# dirtcheaprx.net
KiCad netlist of a schematic drawn in EAGLE
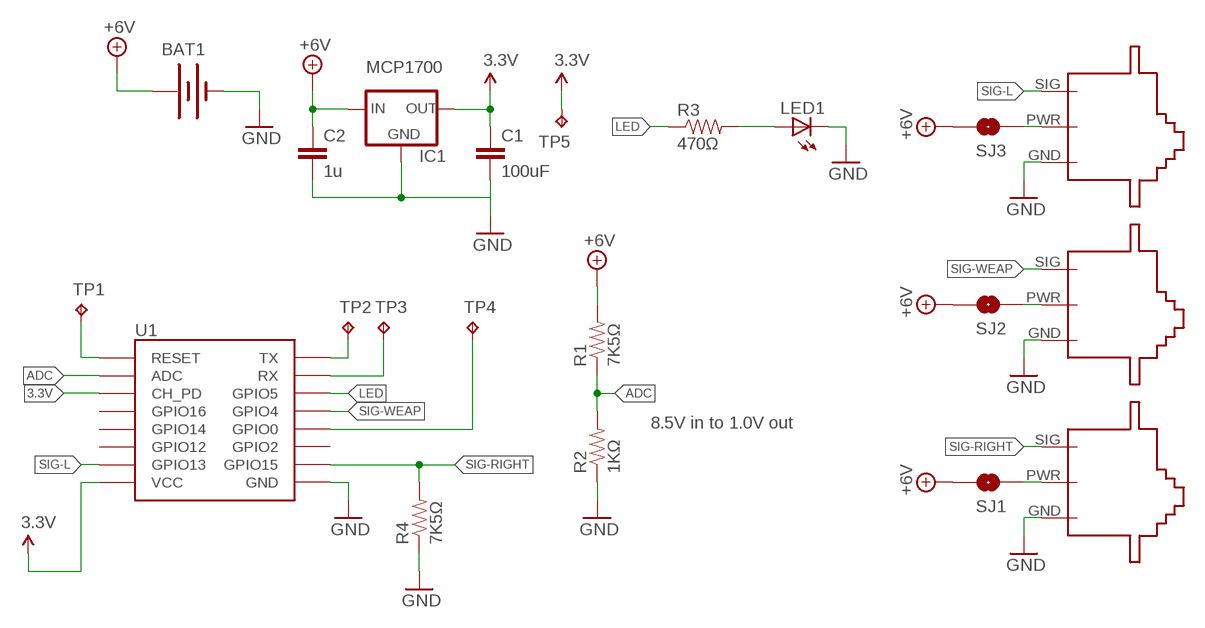
[diagram p0: schematic, sheet 1]

(export (version "E")
  (design (tool "Eeschema 10.0.6"))
  (components
    (comp (ref "BAT1")
      (value "BATTERY-WIRE-CONN")
      (footprint "eagle-import:BATT-WIRE-CONN")
      (libsource (lib "eagle-import") (part "BATTERY-WIRE-CONN"))
    )
    (comp (ref "C1")
      (value "100uF")
      (footprint "eagle-import:0603-CAP")
      (libsource (lib "eagle-import") (part "CAP0603-CAP"))
    )
    (comp (ref "C2")
      (value "1u")
      (footprint "eagle-import:0603-CAP")
      (libsource (lib "eagle-import") (part "CAP0603-CAP"))
    )
    (comp (ref "IC1")
      (value "MCP1700")
      (footprint "eagle-import:SOT23-3")
      (libsource (lib "eagle-import") (part "V_REG_78XX-SOT"))
    )
    (comp (ref "LED1")
      (value "LED5MM")
      (footprint "eagle-import:LED5MM")
      (libsource (lib "eagle-import") (part "LED5MM"))
    )
    (comp (ref "R1")
      (value "7K5Ω")
      (footprint "eagle-import:0603-RES")
      (libsource (lib "eagle-import") (part "RESISTOR0603-RES"))
    )
    (comp (ref "R2")
      (value "1KΩ")
      (footprint "eagle-import:0603-RES")
      (libsource (lib "eagle-import") (part "RESISTOR0603-RES"))
    )
    (comp (ref "R3")
      (value "470Ω")
      (footprint "eagle-import:0603-RES")
      (libsource (lib "eagle-import") (part "RESISTOR0603-RES"))
    )
    (comp (ref "R4")
      (value "7K5Ω")
      (footprint "eagle-import:0603-RES")
      (libsource (lib "eagle-import") (part "RESISTOR0603-RES"))
    )
    (comp (ref "SERVO1")
      (value "SERVO-1")
      (footprint "eagle-import:SERVO")
      (libsource (lib "eagle-import") (part "SERVO-1"))
    )
    (comp (ref "SERVO2")
      (value "SERVO-1")
      (footprint "eagle-import:SERVO")
      (libsource (lib "eagle-import") (part "SERVO-1"))
    )
    (comp (ref "SERVO3")
      (value "SERVO-1")
      (footprint "eagle-import:SERVO")
      (libsource (lib "eagle-import") (part "SERVO-1"))
    )
    (comp (ref "SJ1")
      (value "SOLDERJUMPERNO")
      (footprint "eagle-import:SJ_2S-NO")
      (libsource (lib "eagle-import") (part "SOLDERJUMPERNO"))
    )
    (comp (ref "SJ2")
      (value "SOLDERJUMPERNO")
      (footprint "eagle-import:SJ_2S-NO")
      (libsource (lib "eagle-import") (part "SOLDERJUMPERNO"))
    )
    (comp (ref "SJ3")
      (value "SOLDERJUMPERNO")
      (footprint "eagle-import:SJ_2S-NO")
      (libsource (lib "eagle-import") (part "SOLDERJUMPERNO"))
    )
    (comp (ref "TP1")
      (value "TPPAD1-13")
      (footprint "eagle-import:P1-13")
      (libsource (lib "eagle-import") (part "TPPAD1-13"))
    )
    (comp (ref "TP2")
      (value "TPPAD1-13")
      (footprint "eagle-import:P1-13")
      (libsource (lib "eagle-import") (part "TPPAD1-13"))
    )
    (comp (ref "TP3")
      (value "TPPAD1-13")
      (footprint "eagle-import:P1-13")
      (libsource (lib "eagle-import") (part "TPPAD1-13"))
    )
    (comp (ref "TP4")
      (value "TPPAD1-13")
      (footprint "eagle-import:P1-13")
      (libsource (lib "eagle-import") (part "TPPAD1-13"))
    )
    (comp (ref "TP5")
      (value "TPPAD1-13")
      (footprint "eagle-import:P1-13")
      (libsource (lib "eagle-import") (part "TPPAD1-13"))
    )
    (comp (ref "U1")
      (value "ESP12SMD")
      (footprint "eagle-import:ESP12SE-SMD")
      (libsource (lib "eagle-import") (part "ESP12SMD"))
    )
  )
  (nets
    (net (code "1") (name "+6V") (class "Default")
      (node (ref "BAT1") (pin "POS") (pinfunction "+_POS") (pintype "power_in"))
      (node (ref "C2") (pin "1") (pinfunction "1_1") (pintype "passive"))
      (node (ref "IC1") (pin "3") (pinfunction "IN_3") (pintype "input"))
      (node (ref "R1") (pin "2") (pinfunction "2_2") (pintype "passive"))
      (node (ref "SJ1") (pin "2") (pinfunction "2_2") (pintype "passive"))
      (node (ref "SJ2") (pin "2") (pinfunction "2_2") (pintype "passive"))
      (node (ref "SJ3") (pin "2") (pinfunction "2_2") (pintype "passive"))
    )
    (net (code "2") (name "3.3V") (class "Default")
      (node (ref "C1") (pin "1") (pinfunction "1_1") (pintype "passive"))
      (node (ref "IC1") (pin "2") (pinfunction "OUT_2") (pintype "output"))
      (node (ref "TP5") (pin "TP") (pinfunction "TP_TP") (pintype "input"))
      (node (ref "U1") (pin "CH_PD") (pinfunction "CH_PD_CH_PD") (pintype "bidirectional"))
      (node (ref "U1") (pin "VCC") (pinfunction "VCC_VCC") (pintype "bidirectional"))
    )
    (net (code "3") (name "ADC") (class "Default")
      (node (ref "R1") (pin "1") (pinfunction "1_1") (pintype "passive"))
      (node (ref "R2") (pin "2") (pinfunction "2_2") (pintype "passive"))
      (node (ref "U1") (pin "ADC") (pinfunction "ADC_ADC") (pintype "bidirectional"))
    )
    (net (code "4") (name "GND") (class "Default")
      (node (ref "BAT1") (pin "NEG") (pinfunction "-_NEG") (pintype "power_in"))
      (node (ref "C1") (pin "2") (pinfunction "2_2") (pintype "passive"))
      (node (ref "C2") (pin "2") (pinfunction "2_2") (pintype "passive"))
      (node (ref "IC1") (pin "1") (pinfunction "GND_1") (pintype "input"))
      (node (ref "LED1") (pin "K") (pinfunction "C_K") (pintype "passive"))
      (node (ref "R2") (pin "1") (pinfunction "1_1") (pintype "passive"))
      (node (ref "R4") (pin "1") (pinfunction "1_1") (pintype "passive"))
      (node (ref "SERVO1") (pin "GND") (pinfunction "GND_GND") (pintype "bidirectional"))
      (node (ref "SERVO2") (pin "GND") (pinfunction "GND_GND") (pintype "bidirectional"))
      (node (ref "SERVO3") (pin "GND") (pinfunction "GND_GND") (pintype "bidirectional"))
      (node (ref "U1") (pin "GND") (pinfunction "GND_GND") (pintype "bidirectional"))
    )
    (net (code "5") (name "LED") (class "Default")
      (node (ref "R3") (pin "1") (pinfunction "1_1") (pintype "passive"))
      (node (ref "U1") (pin "GPIO5") (pinfunction "GPIO5_GPIO5") (pintype "bidirectional"))
    )
    (net (code "6") (name "Net-(LED1-PadA)") (class "Default")
      (node (ref "LED1") (pin "A") (pinfunction "A_A") (pintype "passive"))
      (node (ref "R3") (pin "2") (pinfunction "2_2") (pintype "passive"))
    )
    (net (code "7") (name "Net-(SERVO1-PadPWR)") (class "Default")
      (node (ref "SERVO1") (pin "PWR") (pinfunction "PWR_PWR") (pintype "bidirectional"))
      (node (ref "SJ1") (pin "1") (pinfunction "1_1") (pintype "passive"))
    )
    (net (code "8") (name "Net-(SERVO2-PadPWR)") (class "Default")
      (node (ref "SERVO2") (pin "PWR") (pinfunction "PWR_PWR") (pintype "bidirectional"))
      (node (ref "SJ2") (pin "1") (pinfunction "1_1") (pintype "passive"))
    )
    (net (code "9") (name "Net-(SERVO3-PadPWR)") (class "Default")
      (node (ref "SERVO3") (pin "PWR") (pinfunction "PWR_PWR") (pintype "bidirectional"))
      (node (ref "SJ3") (pin "1") (pinfunction "1_1") (pintype "passive"))
    )
    (net (code "10") (name "Net-(TP1-PadTP)") (class "Default")
      (node (ref "TP1") (pin "TP") (pinfunction "TP_TP") (pintype "input"))
      (node (ref "U1") (pin "RESET") (pinfunction "RESET_RESET") (pintype "bidirectional"))
    )
    (net (code "11") (name "Net-(TP4-PadTP)") (class "Default")
      (node (ref "TP4") (pin "TP") (pinfunction "TP_TP") (pintype "input"))
      (node (ref "U1") (pin "GPIO0") (pinfunction "GPIO0_GPIO0") (pintype "bidirectional"))
    )
    (net (code "12") (name "Net-(U1-RX)") (class "Default")
      (node (ref "TP3") (pin "TP") (pinfunction "TP_TP") (pintype "input"))
      (node (ref "U1") (pin "RXD0") (pinfunction "RX_RXD0") (pintype "bidirectional"))
    )
    (net (code "13") (name "Net-(U1-TX)") (class "Default")
      (node (ref "TP2") (pin "TP") (pinfunction "TP_TP") (pintype "input"))
      (node (ref "U1") (pin "TXD0") (pinfunction "TX_TXD0") (pintype "bidirectional"))
    )
    (net (code "14") (name "SIG-L") (class "Default")
      (node (ref "SERVO3") (pin "SIG") (pinfunction "SIG_SIG") (pintype "bidirectional"))
      (node (ref "U1") (pin "GPIO13") (pinfunction "GPIO13_GPIO13") (pintype "bidirectional"))
    )
    (net (code "15") (name "SIG-RIGHT") (class "Default")
      (node (ref "R4") (pin "2") (pinfunction "2_2") (pintype "passive"))
      (node (ref "SERVO1") (pin "SIG") (pinfunction "SIG_SIG") (pintype "bidirectional"))
      (node (ref "U1") (pin "GPIO15") (pinfunction "GPIO15_GPIO15") (pintype "bidirectional"))
    )
    (net (code "16") (name "SIG-WEAP") (class "Default")
      (node (ref "SERVO2") (pin "SIG") (pinfunction "SIG_SIG") (pintype "bidirectional"))
      (node (ref "U1") (pin "GPIO4") (pinfunction "GPIO4_GPIO4") (pintype "bidirectional"))
    )
    (net (code "17") (name "unconnected-(U1-PadGPIO2)") (class "Default")
      (node (ref "U1") (pin "GPIO2") (pinfunction "GPIO2_GPIO2") (pintype "bidirectional"))
    )
    (net (code "18") (name "unconnected-(U1-PadGPIO12)") (class "Default")
      (node (ref "U1") (pin "GPIO12") (pinfunction "GPIO12_GPIO12") (pintype "bidirectional"))
    )
    (net (code "19") (name "unconnected-(U1-PadGPIO14)") (class "Default")
      (node (ref "U1") (pin "GPIO14") (pinfunction "GPIO14_GPIO14") (pintype "bidirectional"))
    )
    (net (code "20") (name "unconnected-(U1-PadGPIO16)") (class "Default")
      (node (ref "U1") (pin "GPIO16") (pinfunction "GPIO16_GPIO16") (pintype "bidirectional"))
    )
  )
)
